# 04_-_CAN.net
KiCad netlist of a schematic drawn in Altium Designer
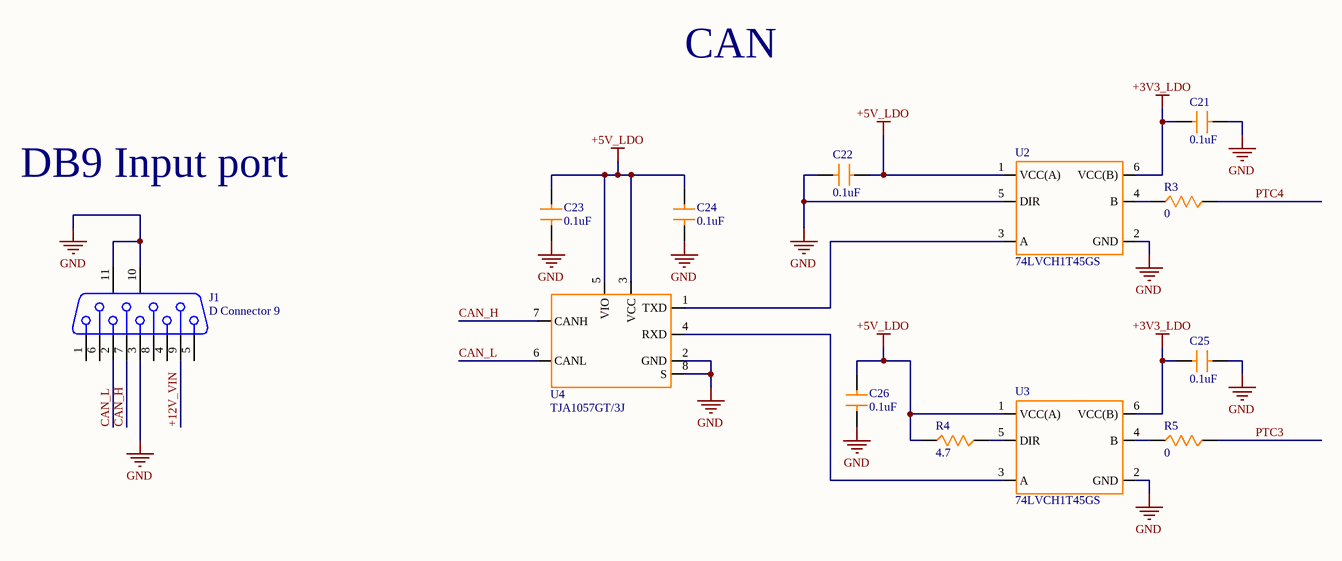
[diagram p0: [04] - CAN.SchDoc]

(export (version "E")
  (design (tool "Eeschema 10.0.6"))
  (components
    (comp (ref "C21")
      (value "0.1uF")
      (footprint "C0805")
      (description "Multilayer Ceramic Capacitors MLCC - SMD/SMT 0.1uF 10% 50V AEC-Q200")
      (fields
        (field (name "MANUFACTURER") "Yageo")
        (field (name "MANUFACTURER PART NUMBER") "AS0805KKX7R9BB104")
      )
      (libsource (lib "Joule_Library") (part "C_0805-0.1uF"))
    )
    (comp (ref "C22")
      (value "0.1uF")
      (footprint "C0805")
      (description "Multilayer Ceramic Capacitors MLCC - SMD/SMT 0.1uF 10% 50V AEC-Q200")
      (fields
        (field (name "MANUFACTURER") "Yageo")
        (field (name "MANUFACTURER PART NUMBER") "AS0805KKX7R9BB104")
      )
      (libsource (lib "Joule_Library") (part "C_0805-0.1uF"))
    )
    (comp (ref "C23")
      (value "0.1uF")
      (footprint "C0805")
      (description "Multilayer Ceramic Capacitors MLCC - SMD/SMT 0.1uF 10% 50V AEC-Q200")
      (fields
        (field (name "MANUFACTURER") "Yageo")
        (field (name "MANUFACTURER PART NUMBER") "AS0805KKX7R9BB104")
      )
      (libsource (lib "Joule_Library") (part "C_0805-0.1uF"))
    )
    (comp (ref "C24")
      (value "0.1uF")
      (footprint "C0805")
      (description "Multilayer Ceramic Capacitors MLCC - SMD/SMT 0.1uF 10% 50V AEC-Q200")
      (fields
        (field (name "MANUFACTURER") "Yageo")
        (field (name "MANUFACTURER PART NUMBER") "AS0805KKX7R9BB104")
      )
      (libsource (lib "Joule_Library") (part "C_0805-0.1uF"))
    )
    (comp (ref "C25")
      (value "0.1uF")
      (footprint "C0805")
      (description "Multilayer Ceramic Capacitors MLCC - SMD/SMT 0.1uF 10% 50V AEC-Q200")
      (fields
        (field (name "MANUFACTURER") "Yageo")
        (field (name "MANUFACTURER PART NUMBER") "AS0805KKX7R9BB104")
      )
      (libsource (lib "Joule_Library") (part "C_0805-0.1uF"))
    )
    (comp (ref "C26")
      (value "0.1uF")
      (footprint "C0805")
      (description "Multilayer Ceramic Capacitors MLCC - SMD/SMT 0.1uF 10% 50V AEC-Q200")
      (fields
        (field (name "MANUFACTURER") "Yageo")
        (field (name "MANUFACTURER PART NUMBER") "AS0805KKX7R9BB104")
      )
      (libsource (lib "Joule_Library") (part "C_0805-0.1uF"))
    )
    (comp (ref "J1")
      (value "D Connector 9")
      (footprint "DSUB1.385-2H9")
      (description "Receptacle Assembly, 9 Position, Right Angle")
      (fields (field (name "PUBLISHER") "Altium Limited"))
      (libsource (lib "Miscellaneous Connectors") (part "D Connector 9"))
    )
    (comp (ref "R3")
      (value "0")
      (footprint "R0805")
      (description "Current Sense Resistors - SMD 0 ohm Jumper 1/2W")
      (fields
        (field (name "MANUFACTURER") "Yageo")
        (field (name "MANUFACTURER PART NUMBER") "PA0805-R-470RL")
      )
      (libsource (lib "Joule_Library") (part "R_0805-0"))
    )
    (comp (ref "R4")
      (value "4.7")
      (footprint "R0805")
      (description "Thin Film Resistors - SMD 4.7 ohm 1% 50 ppm High-Precision")
      (fields
        (field (name "MANUFACTURER") "Yageo")
        (field (name "MANUFACTURER PART NUMBER") "RT0805FRE074R7L")
      )
      (libsource (lib "Joule_Library") (part "R_0805-4.7"))
    )
    (comp (ref "R5")
      (value "0")
      (footprint "R0805")
      (description "Current Sense Resistors - SMD 0 ohm Jumper 1/2W")
      (fields
        (field (name "MANUFACTURER") "Yageo")
        (field (name "MANUFACTURER PART NUMBER") "PA0805-R-470RL")
      )
      (libsource (lib "Joule_Library") (part "R_0805-0"))
    )
    (comp (ref "U2")
      (value "74LVCH1T45GS")
      (footprint "74LVCH1T45GS,132")
      (description "Bus Transceivers 3.6V 250mW 8.2ns")
      (fields
        (field (name "MANUFACTURER") "Nexperia")
        (field (name "MANUFACTURER PART NUMBER") "74LVCH1T45GS,132")
      )
      (libsource (lib "ICs") (part "74LVCH1T45GS,132"))
    )
    (comp (ref "U3")
      (value "74LVCH1T45GS")
      (footprint "74LVCH1T45GS,132")
      (description "Bus Transceivers 3.6V 250mW 8.2ns")
      (fields
        (field (name "MANUFACTURER") "Nexperia")
        (field (name "MANUFACTURER PART NUMBER") "74LVCH1T45GS,132")
      )
      (libsource (lib "ICs") (part "74LVCH1T45GS,132"))
    )
    (comp (ref "U4")
      (value "TJA1057GT/3J")
      (footprint "TJA1057GT/3J")
      (description "CAN Interface IC High-speed CAN transceiver")
      (fields (field (name "MANUFACTURER") "NXP Semiconductors"))
      (libsource (lib "ICs") (part "TJA1057GT/3J"))
    )
  )
  (nets
    (net (code "1") (name "+3V3_LDO") (class "Default")
      (node (ref "C21") (pin "2") (pinfunction "2_2") (pintype "passive"))
      (node (ref "C25") (pin "2") (pinfunction "2_2") (pintype "passive"))
      (node (ref "U2") (pin "6") (pinfunction "VCC(B)_6") (pintype "passive"))
      (node (ref "U3") (pin "6") (pinfunction "VCC(B)_6") (pintype "passive"))
    )
    (net (code "2") (name "+5V_LDO") (class "Default")
      (node (ref "C22") (pin "2") (pinfunction "2_2") (pintype "passive"))
      (node (ref "C23") (pin "2") (pinfunction "2_2") (pintype "passive"))
      (node (ref "C24") (pin "2") (pinfunction "2_2") (pintype "passive"))
      (node (ref "C26") (pin "2") (pinfunction "2_2") (pintype "passive"))
      (node (ref "R4") (pin "1") (pinfunction "1_1") (pintype "passive"))
      (node (ref "U2") (pin "1") (pinfunction "VCC(A)_1") (pintype "passive"))
      (node (ref "U3") (pin "1") (pinfunction "VCC(A)_1") (pintype "passive"))
      (node (ref "U4") (pin "3") (pinfunction "VCC_3") (pintype "passive"))
      (node (ref "U4") (pin "5") (pinfunction "VIO_5") (pintype "passive"))
    )
    (net (code "3") (name "/+12V_VIN") (class "Default")
      (node (ref "J1") (pin "9") (pinfunction "9_9") (pintype "passive"))
    )
    (net (code "4") (name "/CAN_H") (class "Default")
      (node (ref "J1") (pin "7") (pinfunction "7_7") (pintype "passive"))
      (node (ref "U4") (pin "7") (pinfunction "CANH_7") (pintype "passive"))
    )
    (net (code "5") (name "/CAN_L") (class "Default")
      (node (ref "J1") (pin "2") (pinfunction "2_2") (pintype "passive"))
      (node (ref "U4") (pin "6") (pinfunction "CANL_6") (pintype "passive"))
    )
    (net (code "6") (name "/PTC3") (class "Default")
      (node (ref "R5") (pin "2") (pinfunction "2_2") (pintype "passive"))
    )
    (net (code "7") (name "/PTC4") (class "Default")
      (node (ref "R3") (pin "2") (pinfunction "2_2") (pintype "passive"))
    )
    (net (code "8") (name "GND") (class "Default")
      (node (ref "C21") (pin "1") (pinfunction "1_1") (pintype "passive"))
      (node (ref "C22") (pin "1") (pinfunction "1_1") (pintype "passive"))
      (node (ref "C23") (pin "1") (pinfunction "1_1") (pintype "passive"))
      (node (ref "C24") (pin "1") (pinfunction "1_1") (pintype "passive"))
      (node (ref "C25") (pin "1") (pinfunction "1_1") (pintype "passive"))
      (node (ref "C26") (pin "1") (pinfunction "1_1") (pintype "passive"))
      (node (ref "J1") (pin "10") (pinfunction "MH1_10") (pintype "passive"))
      (node (ref "J1") (pin "11") (pinfunction "MH2_11") (pintype "passive"))
      (node (ref "J1") (pin "3") (pinfunction "3_3") (pintype "passive"))
      (node (ref "U2") (pin "2") (pinfunction "GND_2") (pintype "passive"))
      (node (ref "U2") (pin "5") (pinfunction "DIR_5") (pintype "passive"))
      (node (ref "U3") (pin "2") (pinfunction "GND_2") (pintype "passive"))
      (node (ref "U4") (pin "2") (pinfunction "GND_2") (pintype "passive"))
      (node (ref "U4") (pin "8") (pinfunction "S_8") (pintype "passive"))
    )
    (net (code "9") (name "Net-(U2-A)") (class "Default")
      (node (ref "U2") (pin "3") (pinfunction "A_3") (pintype "passive"))
      (node (ref "U4") (pin "1") (pinfunction "TXD_1") (pintype "passive"))
    )
    (net (code "10") (name "Net-(U2-B)") (class "Default")
      (node (ref "R3") (pin "1") (pinfunction "1_1") (pintype "passive"))
      (node (ref "U2") (pin "4") (pinfunction "B_4") (pintype "passive"))
    )
    (net (code "11") (name "Net-(U3-A)") (class "Default")
      (node (ref "U3") (pin "3") (pinfunction "A_3") (pintype "passive"))
      (node (ref "U4") (pin "4") (pinfunction "RXD_4") (pintype "passive"))
    )
    (net (code "12") (name "Net-(U3-B)") (class "Default")
      (node (ref "R5") (pin "1") (pinfunction "1_1") (pintype "passive"))
      (node (ref "U3") (pin "4") (pinfunction "B_4") (pintype "passive"))
    )
    (net (code "13") (name "Net-(U3-DIR)") (class "Default")
      (node (ref "R4") (pin "2") (pinfunction "2_2") (pintype "passive"))
      (node (ref "U3") (pin "5") (pinfunction "DIR_5") (pintype "passive"))
    )
    (net (code "14") (name "unconnected-(J1-Pad1)") (class "Default")
      (node (ref "J1") (pin "1") (pinfunction "1_1") (pintype "passive"))
    )
    (net (code "15") (name "unconnected-(J1-Pad4)") (class "Default")
      (node (ref "J1") (pin "4") (pinfunction "4_4") (pintype "passive"))
    )
    (net (code "16") (name "unconnected-(J1-Pad5)") (class "Default")
      (node (ref "J1") (pin "5") (pinfunction "5_5") (pintype "passive"))
    )
    (net (code "17") (name "unconnected-(J1-Pad6)") (class "Default")
      (node (ref "J1") (pin "6") (pinfunction "6_6") (pintype "passive"))
    )
    (net (code "18") (name "unconnected-(J1-Pad8)") (class "Default")
      (node (ref "J1") (pin "8") (pinfunction "8_8") (pintype "passive"))
    )
  )
)
